# ADCclick.net
KiCad netlist of a schematic drawn in Altium Designer
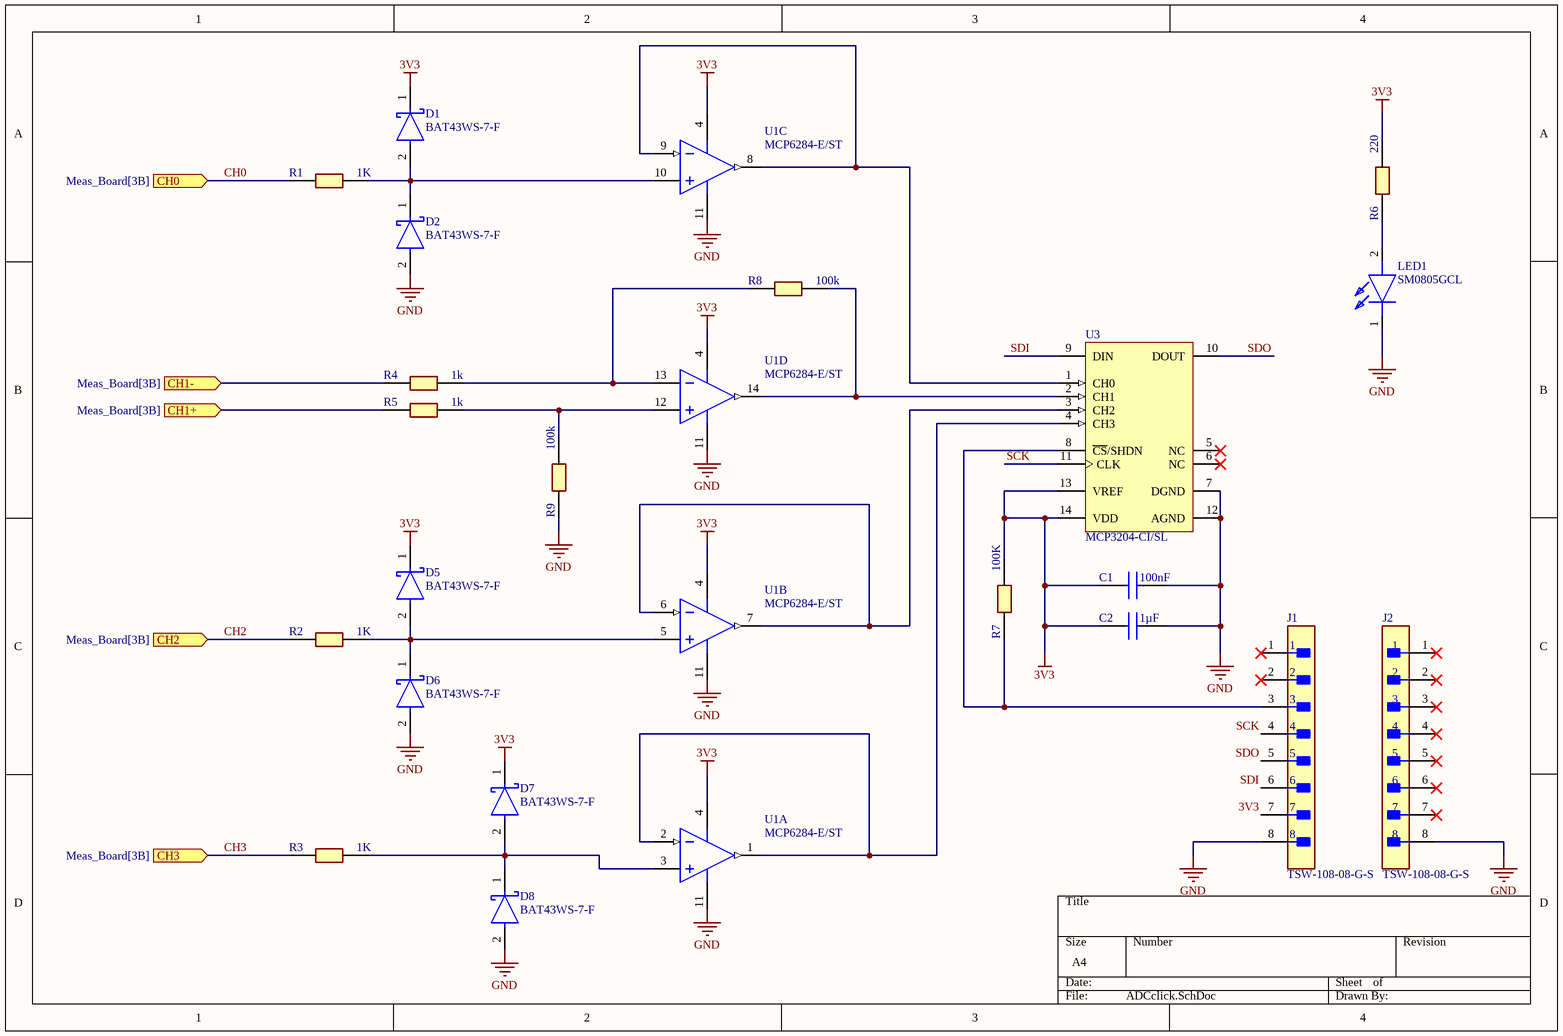
[diagram p0: ADCclick.SchDoc]

(export (version "E")
  (design (tool "Eeschema 10.0.6"))
  (components
    (comp (ref "C1")
      (value "100nF")
      (footprint "IMP_0603")
      (description "Capacitor")
      (fields (field (name "TOLERANCE") "+/-10%") (field (name "Comment") "Cap_Generic"))
      (libsource (lib "Integrated_Library1") (part "Cap_Generic"))
    )
    (comp (ref "C2")
      (value "1µF")
      (footprint "IMP_0805")
      (description "Capacitor")
      (fields (field (name "TOLERANCE") "+/-10%") (field (name "Comment") "Cap_Generic"))
      (libsource (lib "Integrated_Library1") (part "Cap_Generic"))
    )
    (comp (ref "D1")
      (value "BAT43WS-7-F")
      (footprint "FP-SOD323-MFG")
      (description "DIODE SCHOTTKY 30V 200MA SOD323")
      (fields
        (field (name "MANUFACTURER") "Diodes Inc.")
        (field (name "OCTOPART") "https://octopart.com/bat43ws-7-f-diodes+inc.-326114")
      )
      (libsource (lib "Altium Content Vault") (part "1d6ec82d83fb6aee721767c19dac4b9"))
    )
    (comp (ref "D2")
      (value "BAT43WS-7-F")
      (footprint "FP-SOD323-MFG")
      (description "DIODE SCHOTTKY 30V 200MA SOD323")
      (fields
        (field (name "MANUFACTURER") "Diodes Inc.")
        (field (name "OCTOPART") "https://octopart.com/bat43ws-7-f-diodes+inc.-326114")
      )
      (libsource (lib "Altium Content Vault") (part "1d6ec82d83fb6aee721767c19dac4b9"))
    )
    (comp (ref "D5")
      (value "BAT43WS-7-F")
      (footprint "FP-SOD323-MFG")
      (description "DIODE SCHOTTKY 30V 200MA SOD323")
      (fields
        (field (name "MANUFACTURER") "Diodes Inc.")
        (field (name "OCTOPART") "https://octopart.com/bat43ws-7-f-diodes+inc.-326114")
      )
      (libsource (lib "Altium Content Vault") (part "1d6ec82d83fb6aee721767c19dac4b9"))
    )
    (comp (ref "D6")
      (value "BAT43WS-7-F")
      (footprint "FP-SOD323-MFG")
      (description "DIODE SCHOTTKY 30V 200MA SOD323")
      (fields
        (field (name "MANUFACTURER") "Diodes Inc.")
        (field (name "OCTOPART") "https://octopart.com/bat43ws-7-f-diodes+inc.-326114")
      )
      (libsource (lib "Altium Content Vault") (part "1d6ec82d83fb6aee721767c19dac4b9"))
    )
    (comp (ref "D7")
      (value "BAT43WS-7-F")
      (footprint "FP-SOD323-MFG")
      (description "DIODE SCHOTTKY 30V 200MA SOD323")
      (fields
        (field (name "MANUFACTURER") "Diodes Inc.")
        (field (name "OCTOPART") "https://octopart.com/bat43ws-7-f-diodes+inc.-326114")
      )
      (libsource (lib "Altium Content Vault") (part "1d6ec82d83fb6aee721767c19dac4b9"))
    )
    (comp (ref "D8")
      (value "BAT43WS-7-F")
      (footprint "FP-SOD323-MFG")
      (description "DIODE SCHOTTKY 30V 200MA SOD323")
      (fields
        (field (name "MANUFACTURER") "Diodes Inc.")
        (field (name "OCTOPART") "https://octopart.com/bat43ws-7-f-diodes+inc.-326114")
      )
      (libsource (lib "Altium Content Vault") (part "1d6ec82d83fb6aee721767c19dac4b9"))
    )
    (comp (ref "J1")
      (value "TSW-108-08-G-S")
      (footprint "FP-TSW-108-08-G-S-MFG")
      (description "CONN HEADER VERT 8POS 2.54MM")
      (fields
        (field (name "MANUFACTURER") "Samtec")
        (field (name "OCTOPART") "https://octopart.com/tsw-108-08-g-s-samtec-272653")
      )
      (libsource (lib "") (part "99ec2b232beb5d2356d4d77f6a047f0_1"))
    )
    (comp (ref "J2")
      (value "TSW-108-08-G-S")
      (footprint "FP-TSW-108-08-G-S-MFG")
      (description "CONN HEADER VERT 8POS 2.54MM")
      (fields
        (field (name "MANUFACTURER") "Samtec")
        (field (name "OCTOPART") "https://octopart.com/tsw-108-08-g-s-samtec-272653")
      )
      (libsource (lib "Altium Content Vault") (part "99ec2b232beb5d2356d4d77f6a047f0"))
    )
    (comp (ref "LED1")
      (value "SM0805GCL")
      (footprint "LEDC2012X80N")
      (description "LED")
      (fields (field (name "MOUSER PART NUMBER") "749-SM0805GCL"))
      (libsource (lib "Integrated_Library1") (part "SM0805GCL"))
    )
    (comp (ref "R1")
      (value "1K")
      (footprint "IMP-0603")
      (description "Resistor")
      (fields (field (name "TOLERANCE") "+/-1%") (field (name "POWER") "125 mW"))
      (libsource (lib "Integrated_Library1") (part "Res_generic"))
    )
    (comp (ref "R2")
      (value "1K")
      (footprint "IMP-0603")
      (description "Resistor")
      (fields (field (name "TOLERANCE") "+/-1%") (field (name "POWER") "125 mW"))
      (libsource (lib "Integrated_Library1") (part "Res_generic"))
    )
    (comp (ref "R3")
      (value "1K")
      (footprint "IMP-0603")
      (description "Resistor")
      (fields (field (name "TOLERANCE") "+/-1%") (field (name "POWER") "125 mW"))
      (libsource (lib "Integrated_Library1") (part "Res_generic"))
    )
    (comp (ref "R4")
      (value "1k")
      (footprint "IMP-0805")
      (description "Resistor")
      (fields (field (name "TOLERANCE") "+/-1%") (field (name "POWER") "125 mW"))
      (libsource (lib "Integrated_Library1") (part "Res_generic"))
    )
    (comp (ref "R5")
      (value "1k")
      (footprint "IMP-0805")
      (description "Resistor")
      (fields (field (name "TOLERANCE") "+/-1%") (field (name "POWER") "125 mW"))
      (libsource (lib "Integrated_Library1") (part "Res_generic"))
    )
    (comp (ref "R6")
      (value "220")
      (footprint "IMP-0805")
      (description "Resistor")
      (fields (field (name "TOLERANCE") "+/-1%") (field (name "POWER") "125 mW"))
      (libsource (lib "") (part "Res_generic_1"))
    )
    (comp (ref "R7")
      (value "100K")
      (footprint "IMP-0603")
      (description "Resistor")
      (fields (field (name "TOLERANCE") "+/-1%") (field (name "POWER") "125 mW"))
      (libsource (lib "") (part "Res_generic_1"))
    )
    (comp (ref "R8")
      (value "100k")
      (footprint "IMP-0603")
      (description "Resistor")
      (fields (field (name "TOLERANCE") "+/-1%") (field (name "POWER") "125 mW"))
      (libsource (lib "Integrated_Library1") (part "Res_generic"))
    )
    (comp (ref "R9")
      (value "100k")
      (footprint "IMP-0805")
      (description "Resistor")
      (fields (field (name "TOLERANCE") "+/-1%") (field (name "POWER") "125 mW"))
      (libsource (lib "") (part "Res_generic_1"))
    )
    (comp (ref "U1")
      (value "MCP6284-E/ST")
      (footprint "TSSOP-ST14_M")
      (description "None")
      (libsource (lib "Altium Content Vault") (part "AMP-OPA-MCP6284-IL14"))
    )
    (comp (ref "U3")
      (value "MCP3204-CI/SL")
      (footprint "SOIC-SL14_L")
      (libsource (lib "Altium Content Vault") (part "CON-ADC-MCP3004-14"))
    )
  )
  (nets
    (net (code "1") (name "/CH0") (class "Default")
      (node (ref "R1") (pin "1") (pinfunction "1_1") (pintype "passive"))
    )
    (net (code "2") (name "/CH1+") (class "Default")
      (node (ref "R5") (pin "1") (pinfunction "1_1") (pintype "passive"))
    )
    (net (code "3") (name "/CH1-") (class "Default")
      (node (ref "R4") (pin "1") (pinfunction "1_1") (pintype "passive"))
    )
    (net (code "4") (name "/CH2") (class "Default")
      (node (ref "R2") (pin "1") (pinfunction "1_1") (pintype "passive"))
    )
    (net (code "5") (name "/CH3") (class "Default")
      (node (ref "R3") (pin "1") (pinfunction "1_1") (pintype "passive"))
    )
    (net (code "6") (name "/SCK") (class "Default")
      (node (ref "J1") (pin "4") (pinfunction "4_4") (pintype "passive"))
      (node (ref "U3") (pin "11") (pinfunction "CLK_11") (pintype "passive"))
    )
    (net (code "7") (name "/SDI") (class "Default")
      (node (ref "J1") (pin "6") (pinfunction "6_6") (pintype "passive"))
      (node (ref "U3") (pin "9") (pinfunction "DIN_9") (pintype "passive"))
    )
    (net (code "8") (name "/SDO") (class "Default")
      (node (ref "J1") (pin "5") (pinfunction "5_5") (pintype "passive"))
      (node (ref "U3") (pin "10") (pinfunction "DOUT_10") (pintype "tri_state"))
    )
    (net (code "9") (name "3V3") (class "Default")
      (node (ref "C1") (pin "1") (pinfunction "1_1") (pintype "passive"))
      (node (ref "C2") (pin "1") (pinfunction "1_1") (pintype "passive"))
      (node (ref "D1") (pin "1") (pinfunction "C_1") (pintype "passive"))
      (node (ref "D5") (pin "1") (pinfunction "C_1") (pintype "passive"))
      (node (ref "D7") (pin "1") (pinfunction "C_1") (pintype "passive"))
      (node (ref "J1") (pin "7") (pinfunction "7_7") (pintype "passive"))
      (node (ref "R6") (pin "2") (pinfunction "2_2") (pintype "passive"))
      (node (ref "R7") (pin "2") (pinfunction "2_2") (pintype "passive"))
      (node (ref "U1") (pin "4") (pinfunction "VDD_4") (pintype "power_in"))
      (node (ref "U3") (pin "13") (pinfunction "VREF_13") (pintype "passive"))
      (node (ref "U3") (pin "14") (pinfunction "VDD_14") (pintype "power_in"))
    )
    (net (code "10") (name "GND") (class "Default")
      (node (ref "C1") (pin "2") (pinfunction "2_2") (pintype "passive"))
      (node (ref "C2") (pin "2") (pinfunction "2_2") (pintype "passive"))
      (node (ref "D2") (pin "2") (pinfunction "A_2") (pintype "passive"))
      (node (ref "D6") (pin "2") (pinfunction "A_2") (pintype "passive"))
      (node (ref "D8") (pin "2") (pinfunction "A_2") (pintype "passive"))
      (node (ref "J1") (pin "8") (pinfunction "8_8") (pintype "passive"))
      (node (ref "J2") (pin "8") (pinfunction "8_8") (pintype "passive"))
      (node (ref "LED1") (pin "1") (pinfunction "K_1") (pintype "passive"))
      (node (ref "R9") (pin "1") (pinfunction "1_1") (pintype "passive"))
      (node (ref "U1") (pin "11") (pinfunction "VSS_11") (pintype "power_in"))
      (node (ref "U3") (pin "12") (pinfunction "AGND_12") (pintype "power_in"))
      (node (ref "U3") (pin "7") (pinfunction "DGND_7") (pintype "power_in"))
    )
    (net (code "11") (name "Net-(D1-A)") (class "Default")
      (node (ref "D1") (pin "2") (pinfunction "A_2") (pintype "passive"))
      (node (ref "D2") (pin "1") (pinfunction "C_1") (pintype "passive"))
      (node (ref "R1") (pin "2") (pinfunction "2_2") (pintype "passive"))
      (node (ref "U1") (pin "10") (pinfunction "VINC+_10") (pintype "input"))
    )
    (net (code "12") (name "Net-(D5-A)") (class "Default")
      (node (ref "D5") (pin "2") (pinfunction "A_2") (pintype "passive"))
      (node (ref "D6") (pin "1") (pinfunction "C_1") (pintype "passive"))
      (node (ref "R2") (pin "2") (pinfunction "2_2") (pintype "passive"))
      (node (ref "U1") (pin "5") (pinfunction "VINB+_5") (pintype "passive"))
    )
    (net (code "13") (name "Net-(D7-A)") (class "Default")
      (node (ref "D7") (pin "2") (pinfunction "A_2") (pintype "passive"))
      (node (ref "D8") (pin "1") (pinfunction "C_1") (pintype "passive"))
      (node (ref "R3") (pin "2") (pinfunction "2_2") (pintype "passive"))
      (node (ref "U1") (pin "3") (pinfunction "VINA+_3") (pintype "input"))
    )
    (net (code "14") (name "Net-(LED1-A)") (class "Default")
      (node (ref "LED1") (pin "2") (pinfunction "A_2") (pintype "passive"))
      (node (ref "R6") (pin "1") (pinfunction "1_1") (pintype "passive"))
    )
    (net (code "15") (name "Net-(U1A-VINA-)") (class "Default")
      (node (ref "U1") (pin "1") (pinfunction "VOUTA_1") (pintype "output"))
      (node (ref "U1") (pin "2") (pinfunction "VINA-_2") (pintype "input"))
      (node (ref "U3") (pin "4") (pinfunction "CH3_4") (pintype "input"))
    )
    (net (code "16") (name "Net-(U1B-VINB-)") (class "Default")
      (node (ref "U1") (pin "6") (pinfunction "VINB-_6") (pintype "input"))
      (node (ref "U1") (pin "7") (pinfunction "VOUTB_7") (pintype "output"))
      (node (ref "U3") (pin "3") (pinfunction "CH2_3") (pintype "input"))
    )
    (net (code "17") (name "Net-(U1C-VINC-)") (class "Default")
      (node (ref "U1") (pin "8") (pinfunction "VOUTC_8") (pintype "output"))
      (node (ref "U1") (pin "9") (pinfunction "VINC-_9") (pintype "input"))
      (node (ref "U3") (pin "1") (pinfunction "CH0_1") (pintype "input"))
    )
    (net (code "18") (name "Net-(U1D-VIND+)") (class "Default")
      (node (ref "R5") (pin "2") (pinfunction "2_2") (pintype "passive"))
      (node (ref "R9") (pin "2") (pinfunction "2_2") (pintype "passive"))
      (node (ref "U1") (pin "12") (pinfunction "VIND+_12") (pintype "input"))
    )
    (net (code "19") (name "Net-(U1D-VIND-)") (class "Default")
      (node (ref "R4") (pin "2") (pinfunction "2_2") (pintype "passive"))
      (node (ref "R8") (pin "1") (pinfunction "1_1") (pintype "passive"))
      (node (ref "U1") (pin "13") (pinfunction "VIND-_13") (pintype "input"))
    )
    (net (code "20") (name "Net-(U1D-VOUTD)") (class "Default")
      (node (ref "R8") (pin "2") (pinfunction "2_2") (pintype "passive"))
      (node (ref "U1") (pin "14") (pinfunction "VOUTD_14") (pintype "output"))
      (node (ref "U3") (pin "2") (pinfunction "CH1_2") (pintype "input"))
    )
    (net (code "21") (name "Net-(U3-~{CS}{slash}SHDN)") (class "Default")
      (node (ref "J1") (pin "3") (pinfunction "3_3") (pintype "passive"))
      (node (ref "R7") (pin "1") (pinfunction "1_1") (pintype "passive"))
      (node (ref "U3") (pin "8") (pinfunction "~{CS}/SHDN_8") (pintype "passive"))
    )
    (net (code "22") (name "unconnected-(J1-Pad1)") (class "Default")
      (node (ref "J1") (pin "1") (pinfunction "1_1") (pintype "passive+no_connect"))
    )
    (net (code "23") (name "unconnected-(J1-Pad2)") (class "Default")
      (node (ref "J1") (pin "2") (pinfunction "2_2") (pintype "passive+no_connect"))
    )
    (net (code "24") (name "unconnected-(J2-Pad1)") (class "Default")
      (node (ref "J2") (pin "1") (pinfunction "1_1") (pintype "passive+no_connect"))
    )
    (net (code "25") (name "unconnected-(J2-Pad2)") (class "Default")
      (node (ref "J2") (pin "2") (pinfunction "2_2") (pintype "passive+no_connect"))
    )
    (net (code "26") (name "unconnected-(J2-Pad3)") (class "Default")
      (node (ref "J2") (pin "3") (pinfunction "3_3") (pintype "passive+no_connect"))
    )
    (net (code "27") (name "unconnected-(J2-Pad4)") (class "Default")
      (node (ref "J2") (pin "4") (pinfunction "4_4") (pintype "passive+no_connect"))
    )
    (net (code "28") (name "unconnected-(J2-Pad5)") (class "Default")
      (node (ref "J2") (pin "5") (pinfunction "5_5") (pintype "passive+no_connect"))
    )
    (net (code "29") (name "unconnected-(J2-Pad6)") (class "Default")
      (node (ref "J2") (pin "6") (pinfunction "6_6") (pintype "passive+no_connect"))
    )
    (net (code "30") (name "unconnected-(J2-Pad7)") (class "Default")
      (node (ref "J2") (pin "7") (pinfunction "7_7") (pintype "passive+no_connect"))
    )
    (net (code "31") (name "unconnected-(U3-NC-Pad5)") (class "Default")
      (node (ref "U3") (pin "5") (pinfunction "NC_5") (pintype "passive+no_connect"))
    )
    (net (code "32") (name "unconnected-(U3-NC-Pad6)") (class "Default")
      (node (ref "U3") (pin "6") (pinfunction "NC_6") (pintype "passive+no_connect"))
    )
  )
)
